# para.net
KiCad netlist of a schematic drawn in EAGLE
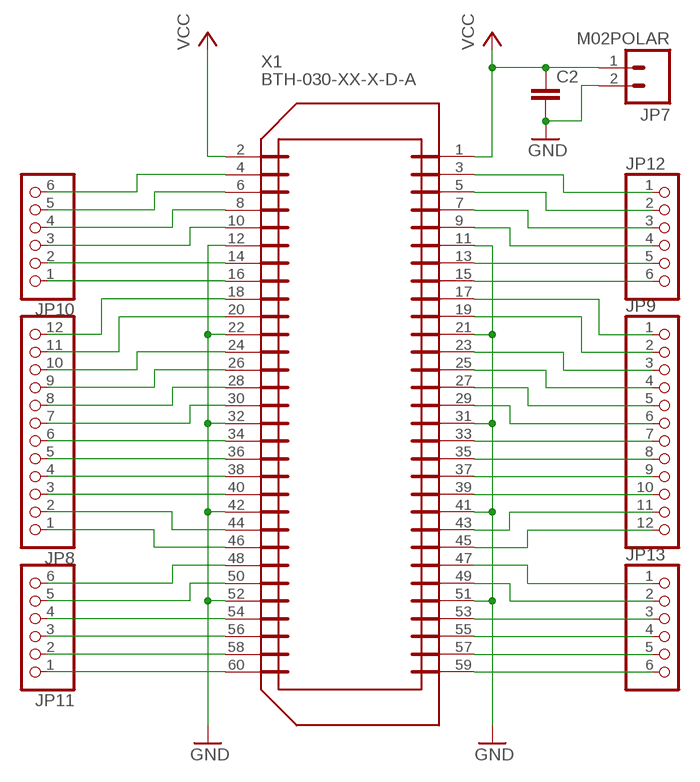
[diagram p0: schematic, sheet 1]

(export (version "E")
  (design (tool "Eeschema 10.0.6"))
  (components
    (comp (ref "C2")
      (value "CAP0805")
      (footprint "eagle-import:0805")
      (libsource (lib "eagle-import") (part "CAP0805"))
    )
    (comp (ref "JP7")
      (value "M02POLAR")
      (footprint "eagle-import:MOLEX-1X2")
      (libsource (lib "eagle-import") (part "M02POLAR"))
    )
    (comp (ref "JP8")
      (value "PINHD-1X12-CB")
      (footprint "eagle-import:1X12-CB")
      (libsource (lib "eagle-import") (part "PINHD-1X12-CB"))
    )
    (comp (ref "JP9")
      (value "PINHD-1X12-CB")
      (footprint "eagle-import:1X12-CB")
      (libsource (lib "eagle-import") (part "PINHD-1X12-CB"))
    )
    (comp (ref "JP10")
      (value "PINHD-1X6CB")
      (footprint "eagle-import:1X06-CLEANBIG")
      (libsource (lib "eagle-import") (part "PINHD-1X6CB"))
    )
    (comp (ref "JP11")
      (value "PINHD-1X6CB")
      (footprint "eagle-import:1X06-CLEANBIG")
      (libsource (lib "eagle-import") (part "PINHD-1X6CB"))
    )
    (comp (ref "JP12")
      (value "PINHD-1X6CB")
      (footprint "eagle-import:1X06-CLEANBIG")
      (libsource (lib "eagle-import") (part "PINHD-1X6CB"))
    )
    (comp (ref "JP13")
      (value "PINHD-1X6CB")
      (footprint "eagle-import:1X06-CLEANBIG")
      (libsource (lib "eagle-import") (part "PINHD-1X6CB"))
    )
    (comp (ref "X1")
      (value "BTH-030-XX-X-D-A")
      (footprint "eagle-import:BTH-030-XX-X-D-A")
      (libsource (lib "eagle-import") (part "BTH-030-XX-X-D-A"))
    )
  )
  (nets
    (net (code "1") (name "GND") (class "Default")
      (node (ref "C2") (pin "2") (pinfunction "2_2") (pintype "passive"))
      (node (ref "JP7") (pin "2") (pinfunction "2_2") (pintype "passive"))
      (node (ref "X1") (pin "11") (pinfunction "11_11") (pintype "passive"))
      (node (ref "X1") (pin "12") (pinfunction "12_12") (pintype "passive"))
      (node (ref "X1") (pin "21") (pinfunction "21_21") (pintype "passive"))
      (node (ref "X1") (pin "22") (pinfunction "22_22") (pintype "passive"))
      (node (ref "X1") (pin "31") (pinfunction "31_31") (pintype "passive"))
      (node (ref "X1") (pin "32") (pinfunction "32_32") (pintype "passive"))
      (node (ref "X1") (pin "41") (pinfunction "41_41") (pintype "passive"))
      (node (ref "X1") (pin "42") (pinfunction "42_42") (pintype "passive"))
      (node (ref "X1") (pin "51") (pinfunction "51_51") (pintype "passive"))
      (node (ref "X1") (pin "52") (pinfunction "52_52") (pintype "passive"))
    )
    (net (code "2") (name "Net-(JP8-Pad1)") (class "Default")
      (node (ref "JP8") (pin "1") (pinfunction "1_1") (pintype "passive"))
      (node (ref "X1") (pin "46") (pinfunction "46_46") (pintype "passive"))
    )
    (net (code "3") (name "Net-(JP8-Pad2)") (class "Default")
      (node (ref "JP8") (pin "2") (pinfunction "2_2") (pintype "passive"))
      (node (ref "X1") (pin "44") (pinfunction "44_44") (pintype "passive"))
    )
    (net (code "4") (name "Net-(JP8-Pad3)") (class "Default")
      (node (ref "JP8") (pin "3") (pinfunction "3_3") (pintype "passive"))
      (node (ref "X1") (pin "40") (pinfunction "40_40") (pintype "passive"))
    )
    (net (code "5") (name "Net-(JP8-Pad4)") (class "Default")
      (node (ref "JP8") (pin "4") (pinfunction "4_4") (pintype "passive"))
      (node (ref "X1") (pin "38") (pinfunction "38_38") (pintype "passive"))
    )
    (net (code "6") (name "Net-(JP8-Pad5)") (class "Default")
      (node (ref "JP8") (pin "5") (pinfunction "5_5") (pintype "passive"))
      (node (ref "X1") (pin "36") (pinfunction "36_36") (pintype "passive"))
    )
    (net (code "7") (name "Net-(JP8-Pad6)") (class "Default")
      (node (ref "JP8") (pin "6") (pinfunction "6_6") (pintype "passive"))
      (node (ref "X1") (pin "34") (pinfunction "34_34") (pintype "passive"))
    )
    (net (code "8") (name "Net-(JP8-Pad7)") (class "Default")
      (node (ref "JP8") (pin "7") (pinfunction "7_7") (pintype "passive"))
      (node (ref "X1") (pin "30") (pinfunction "30_30") (pintype "passive"))
    )
    (net (code "9") (name "Net-(JP8-Pad8)") (class "Default")
      (node (ref "JP8") (pin "8") (pinfunction "8_8") (pintype "passive"))
      (node (ref "X1") (pin "28") (pinfunction "28_28") (pintype "passive"))
    )
    (net (code "10") (name "Net-(JP8-Pad9)") (class "Default")
      (node (ref "JP8") (pin "9") (pinfunction "9_9") (pintype "passive"))
      (node (ref "X1") (pin "26") (pinfunction "26_26") (pintype "passive"))
    )
    (net (code "11") (name "Net-(JP8-Pad10)") (class "Default")
      (node (ref "JP8") (pin "10") (pinfunction "10_10") (pintype "passive"))
      (node (ref "X1") (pin "24") (pinfunction "24_24") (pintype "passive"))
    )
    (net (code "12") (name "Net-(JP8-Pad11)") (class "Default")
      (node (ref "JP8") (pin "11") (pinfunction "11_11") (pintype "passive"))
      (node (ref "X1") (pin "20") (pinfunction "20_20") (pintype "passive"))
    )
    (net (code "13") (name "Net-(JP8-Pad12)") (class "Default")
      (node (ref "JP8") (pin "12") (pinfunction "12_12") (pintype "passive"))
      (node (ref "X1") (pin "18") (pinfunction "18_18") (pintype "passive"))
    )
    (net (code "14") (name "Net-(JP9-Pad1)") (class "Default")
      (node (ref "JP9") (pin "1") (pinfunction "1_1") (pintype "passive"))
      (node (ref "X1") (pin "17") (pinfunction "17_17") (pintype "passive"))
    )
    (net (code "15") (name "Net-(JP9-Pad2)") (class "Default")
      (node (ref "JP9") (pin "2") (pinfunction "2_2") (pintype "passive"))
      (node (ref "X1") (pin "19") (pinfunction "19_19") (pintype "passive"))
    )
    (net (code "16") (name "Net-(JP9-Pad3)") (class "Default")
      (node (ref "JP9") (pin "3") (pinfunction "3_3") (pintype "passive"))
      (node (ref "X1") (pin "23") (pinfunction "23_23") (pintype "passive"))
    )
    (net (code "17") (name "Net-(JP9-Pad4)") (class "Default")
      (node (ref "JP9") (pin "4") (pinfunction "4_4") (pintype "passive"))
      (node (ref "X1") (pin "25") (pinfunction "25_25") (pintype "passive"))
    )
    (net (code "18") (name "Net-(JP9-Pad5)") (class "Default")
      (node (ref "JP9") (pin "5") (pinfunction "5_5") (pintype "passive"))
      (node (ref "X1") (pin "27") (pinfunction "27_27") (pintype "passive"))
    )
    (net (code "19") (name "Net-(JP9-Pad6)") (class "Default")
      (node (ref "JP9") (pin "6") (pinfunction "6_6") (pintype "passive"))
      (node (ref "X1") (pin "29") (pinfunction "29_29") (pintype "passive"))
    )
    (net (code "20") (name "Net-(JP9-Pad7)") (class "Default")
      (node (ref "JP9") (pin "7") (pinfunction "7_7") (pintype "passive"))
      (node (ref "X1") (pin "33") (pinfunction "33_33") (pintype "passive"))
    )
    (net (code "21") (name "Net-(JP9-Pad8)") (class "Default")
      (node (ref "JP9") (pin "8") (pinfunction "8_8") (pintype "passive"))
      (node (ref "X1") (pin "35") (pinfunction "35_35") (pintype "passive"))
    )
    (net (code "22") (name "Net-(JP9-Pad9)") (class "Default")
      (node (ref "JP9") (pin "9") (pinfunction "9_9") (pintype "passive"))
      (node (ref "X1") (pin "37") (pinfunction "37_37") (pintype "passive"))
    )
    (net (code "23") (name "Net-(JP9-Pad10)") (class "Default")
      (node (ref "JP9") (pin "10") (pinfunction "10_10") (pintype "passive"))
      (node (ref "X1") (pin "39") (pinfunction "39_39") (pintype "passive"))
    )
    (net (code "24") (name "Net-(JP9-Pad11)") (class "Default")
      (node (ref "JP9") (pin "11") (pinfunction "11_11") (pintype "passive"))
      (node (ref "X1") (pin "43") (pinfunction "43_43") (pintype "passive"))
    )
    (net (code "25") (name "Net-(JP9-Pad12)") (class "Default")
      (node (ref "JP9") (pin "12") (pinfunction "12_12") (pintype "passive"))
      (node (ref "X1") (pin "45") (pinfunction "45_45") (pintype "passive"))
    )
    (net (code "26") (name "Net-(JP10-Pad1)") (class "Default")
      (node (ref "JP10") (pin "1") (pinfunction "1_1") (pintype "passive"))
      (node (ref "X1") (pin "16") (pinfunction "16_16") (pintype "passive"))
    )
    (net (code "27") (name "Net-(JP10-Pad2)") (class "Default")
      (node (ref "JP10") (pin "2") (pinfunction "2_2") (pintype "passive"))
      (node (ref "X1") (pin "14") (pinfunction "14_14") (pintype "passive"))
    )
    (net (code "28") (name "Net-(JP10-Pad3)") (class "Default")
      (node (ref "JP10") (pin "3") (pinfunction "3_3") (pintype "passive"))
      (node (ref "X1") (pin "10") (pinfunction "10_10") (pintype "passive"))
    )
    (net (code "29") (name "Net-(JP10-Pad4)") (class "Default")
      (node (ref "JP10") (pin "4") (pinfunction "4_4") (pintype "passive"))
      (node (ref "X1") (pin "8") (pinfunction "8_8") (pintype "passive"))
    )
    (net (code "30") (name "Net-(JP10-Pad5)") (class "Default")
      (node (ref "JP10") (pin "5") (pinfunction "5_5") (pintype "passive"))
      (node (ref "X1") (pin "6") (pinfunction "6_6") (pintype "passive"))
    )
    (net (code "31") (name "Net-(JP10-Pad6)") (class "Default")
      (node (ref "JP10") (pin "6") (pinfunction "6_6") (pintype "passive"))
      (node (ref "X1") (pin "4") (pinfunction "4_4") (pintype "passive"))
    )
    (net (code "32") (name "Net-(JP11-Pad1)") (class "Default")
      (node (ref "JP11") (pin "1") (pinfunction "1_1") (pintype "passive"))
      (node (ref "X1") (pin "60") (pinfunction "60_60") (pintype "passive"))
    )
    (net (code "33") (name "Net-(JP11-Pad2)") (class "Default")
      (node (ref "JP11") (pin "2") (pinfunction "2_2") (pintype "passive"))
      (node (ref "X1") (pin "58") (pinfunction "58_58") (pintype "passive"))
    )
    (net (code "34") (name "Net-(JP11-Pad3)") (class "Default")
      (node (ref "JP11") (pin "3") (pinfunction "3_3") (pintype "passive"))
      (node (ref "X1") (pin "56") (pinfunction "56_56") (pintype "passive"))
    )
    (net (code "35") (name "Net-(JP11-Pad4)") (class "Default")
      (node (ref "JP11") (pin "4") (pinfunction "4_4") (pintype "passive"))
      (node (ref "X1") (pin "54") (pinfunction "54_54") (pintype "passive"))
    )
    (net (code "36") (name "Net-(JP11-Pad5)") (class "Default")
      (node (ref "JP11") (pin "5") (pinfunction "5_5") (pintype "passive"))
      (node (ref "X1") (pin "50") (pinfunction "50_50") (pintype "passive"))
    )
    (net (code "37") (name "Net-(JP11-Pad6)") (class "Default")
      (node (ref "JP11") (pin "6") (pinfunction "6_6") (pintype "passive"))
      (node (ref "X1") (pin "48") (pinfunction "48_48") (pintype "passive"))
    )
    (net (code "38") (name "Net-(JP12-Pad1)") (class "Default")
      (node (ref "JP12") (pin "1") (pinfunction "1_1") (pintype "passive"))
      (node (ref "X1") (pin "3") (pinfunction "3_3") (pintype "passive"))
    )
    (net (code "39") (name "Net-(JP12-Pad2)") (class "Default")
      (node (ref "JP12") (pin "2") (pinfunction "2_2") (pintype "passive"))
      (node (ref "X1") (pin "5") (pinfunction "5_5") (pintype "passive"))
    )
    (net (code "40") (name "Net-(JP12-Pad3)") (class "Default")
      (node (ref "JP12") (pin "3") (pinfunction "3_3") (pintype "passive"))
      (node (ref "X1") (pin "7") (pinfunction "7_7") (pintype "passive"))
    )
    (net (code "41") (name "Net-(JP12-Pad4)") (class "Default")
      (node (ref "JP12") (pin "4") (pinfunction "4_4") (pintype "passive"))
      (node (ref "X1") (pin "9") (pinfunction "9_9") (pintype "passive"))
    )
    (net (code "42") (name "Net-(JP12-Pad5)") (class "Default")
      (node (ref "JP12") (pin "5") (pinfunction "5_5") (pintype "passive"))
      (node (ref "X1") (pin "13") (pinfunction "13_13") (pintype "passive"))
    )
    (net (code "43") (name "Net-(JP12-Pad6)") (class "Default")
      (node (ref "JP12") (pin "6") (pinfunction "6_6") (pintype "passive"))
      (node (ref "X1") (pin "15") (pinfunction "15_15") (pintype "passive"))
    )
    (net (code "44") (name "Net-(JP13-Pad1)") (class "Default")
      (node (ref "JP13") (pin "1") (pinfunction "1_1") (pintype "passive"))
      (node (ref "X1") (pin "47") (pinfunction "47_47") (pintype "passive"))
    )
    (net (code "45") (name "Net-(JP13-Pad2)") (class "Default")
      (node (ref "JP13") (pin "2") (pinfunction "2_2") (pintype "passive"))
      (node (ref "X1") (pin "49") (pinfunction "49_49") (pintype "passive"))
    )
    (net (code "46") (name "Net-(JP13-Pad3)") (class "Default")
      (node (ref "JP13") (pin "3") (pinfunction "3_3") (pintype "passive"))
      (node (ref "X1") (pin "53") (pinfunction "53_53") (pintype "passive"))
    )
    (net (code "47") (name "Net-(JP13-Pad4)") (class "Default")
      (node (ref "JP13") (pin "4") (pinfunction "4_4") (pintype "passive"))
      (node (ref "X1") (pin "55") (pinfunction "55_55") (pintype "passive"))
    )
    (net (code "48") (name "Net-(JP13-Pad5)") (class "Default")
      (node (ref "JP13") (pin "5") (pinfunction "5_5") (pintype "passive"))
      (node (ref "X1") (pin "57") (pinfunction "57_57") (pintype "passive"))
    )
    (net (code "49") (name "Net-(JP13-Pad6)") (class "Default")
      (node (ref "JP13") (pin "6") (pinfunction "6_6") (pintype "passive"))
      (node (ref "X1") (pin "59") (pinfunction "59_59") (pintype "passive"))
    )
    (net (code "50") (name "VCC") (class "Default")
      (node (ref "C2") (pin "1") (pinfunction "1_1") (pintype "passive"))
      (node (ref "JP7") (pin "1") (pinfunction "1_1") (pintype "passive"))
      (node (ref "X1") (pin "1") (pinfunction "1_1") (pintype "passive"))
      (node (ref "X1") (pin "2") (pinfunction "2_2") (pintype "passive"))
    )
  )
)
